# Schematics_2.net
KiCad netlist of a schematic drawn in EasyEDA
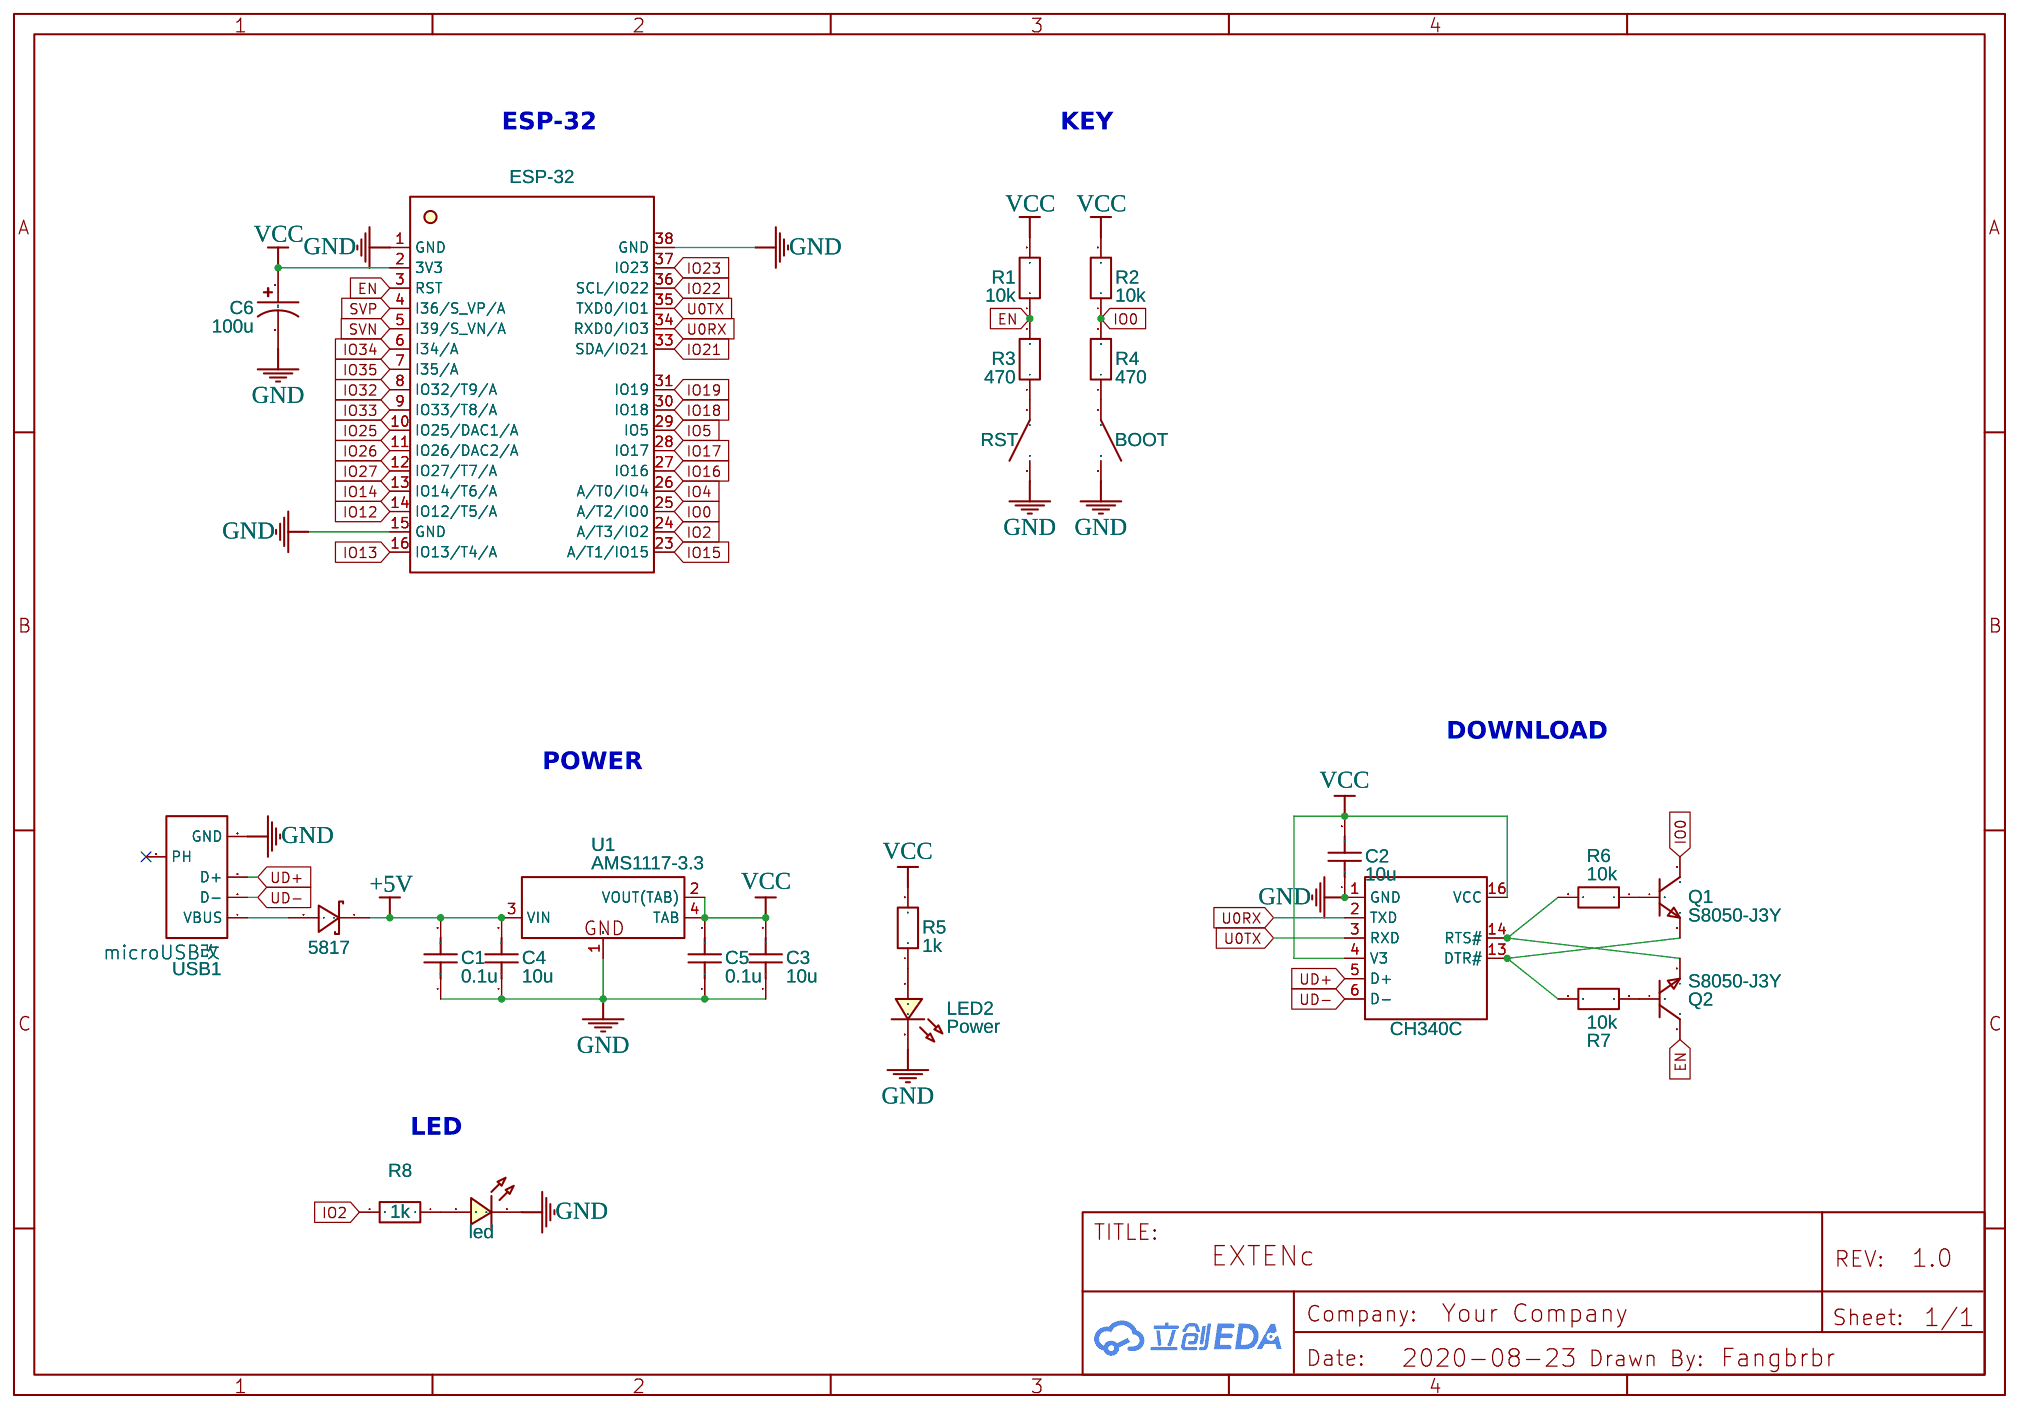
[diagram p0: Sheet_1]
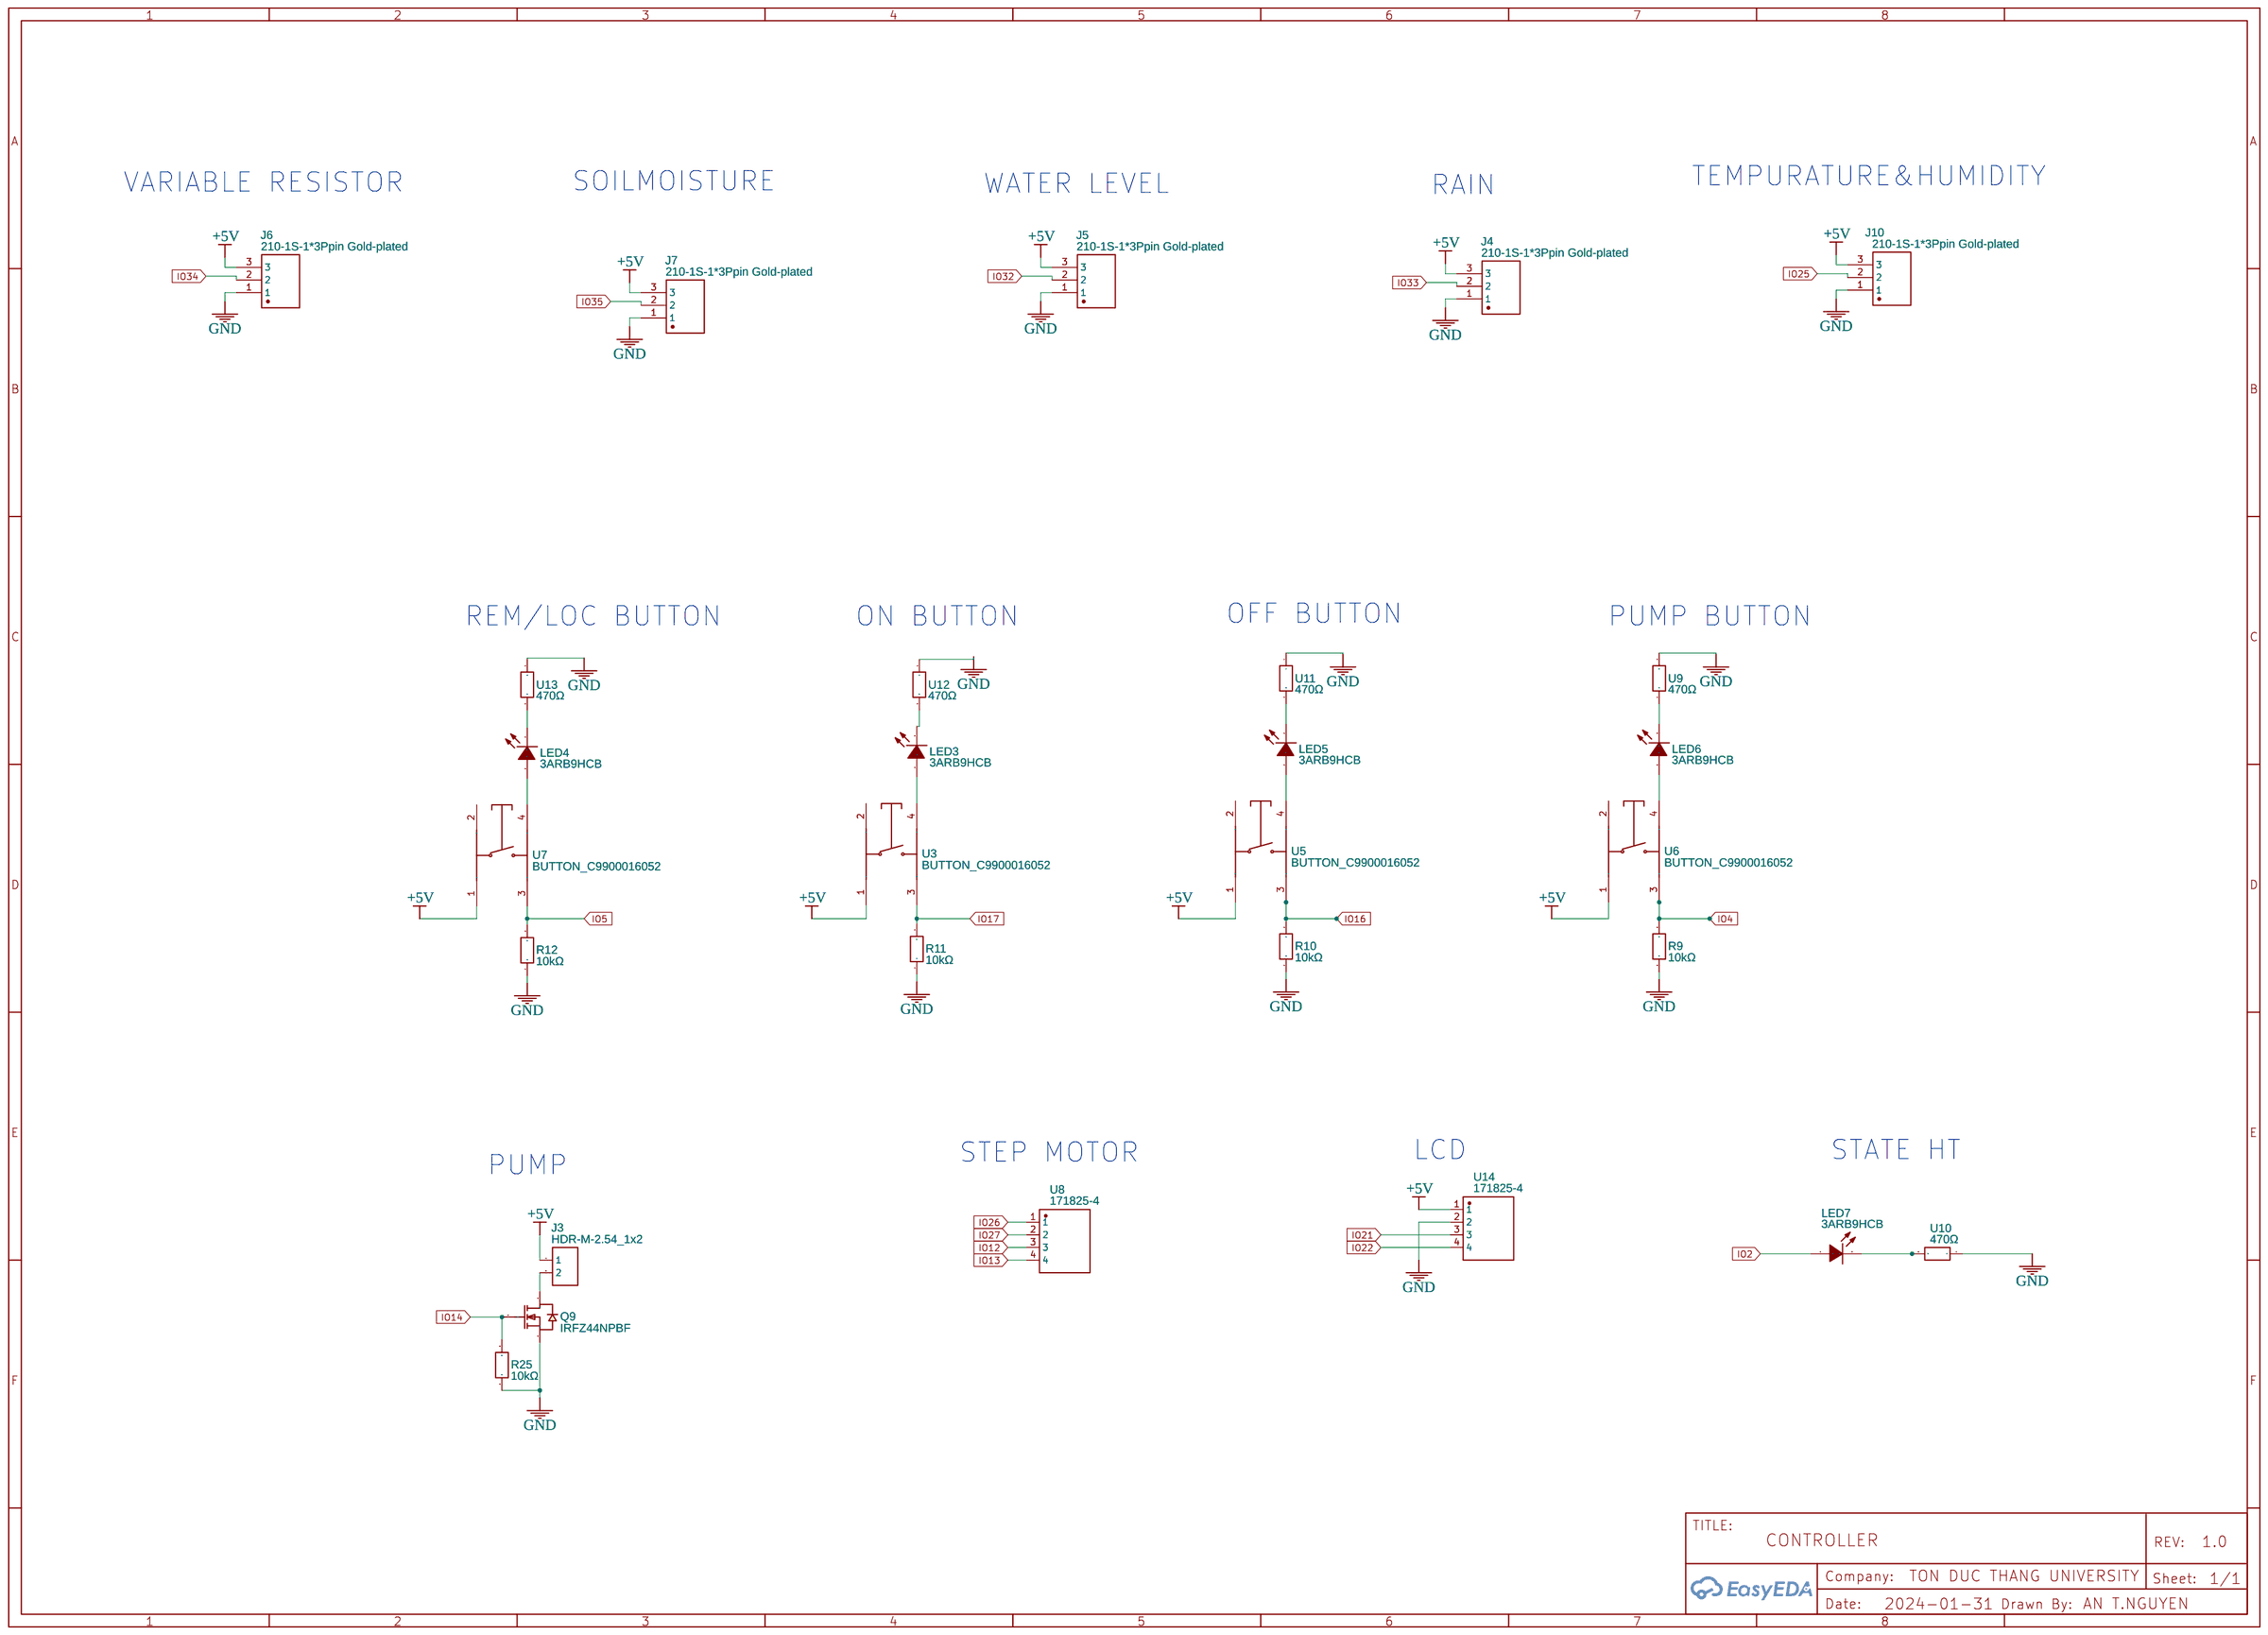
[diagram p1: Sheet_2]

(export (version "E")
  (design (tool "Eeschema 10.0.6"))
  (components
    (comp (ref "C1") (value "0.1u") (libsource (lib "") (part "C_0603_US")))
    (comp (ref "C2") (value "10u") (libsource (lib "") (part "C_0603_US")))
    (comp (ref "C3") (value "10u") (libsource (lib "") (part "C_0603_US")))
    (comp (ref "C4") (value "10u") (libsource (lib "") (part "C_0603_US")))
    (comp (ref "C5") (value "0.1u") (libsource (lib "") (part "C_0603_US")))
    (comp (ref "C6") (value "100u") (libsource (lib "") (part "C_Tan_SMD_B_US")))
    (comp (ref "D1")
      (value "5817")
      (fields
        (field (name "Manufacturer Part") "1N5819W")
        (field (name "Manufacturer") "Shandong Jingdao Microelectronics")
      )
      (libsource (lib "") (part "1N5819W"))
    )
    (comp (ref "LED1")
      (value "led")
      (fields
        (field (name "Manufacturer Part") "19-217/R6C-AL1M2VY/3T")
        (field (name "Manufacturer") "EVERLIGHT(台湾亿光)")
      )
      (libsource (lib "") (part "LED-0603_R"))
    )
    (comp (ref "LED2")
      (value "Power")
      (fields
        (field (name "Manufacturer Part") "19-217/R6C-AL1M2VY/3T")
        (field (name "Manufacturer") "EVERLIGHT(台湾亿光)")
      )
      (libsource (lib "") (part "LED-0603_R_1"))
    )
    (comp (ref "Q1")
      (value "S8050-J3Y")
      (fields (field (name "Manufacturer") "(MDD) Jiangsu Yutai Elec"))
      (libsource (lib "") (part "S8050-J3Y"))
    )
    (comp (ref "Q2")
      (value "S8050-J3Y")
      (fields (field (name "Manufacturer") "(MDD) Jiangsu Yutai Elec"))
      (libsource (lib "") (part "S8050-J3Y_1"))
    )
    (comp (ref "R1") (value "10k") (libsource (lib "") (part "R_0603_EU")))
    (comp (ref "R2") (value "10k") (libsource (lib "") (part "R_0603_EU")))
    (comp (ref "R3") (value "470") (libsource (lib "") (part "R_0603_EU")))
    (comp (ref "R4") (value "470") (libsource (lib "") (part "R_0603_EU")))
    (comp (ref "R5") (value "1k") (libsource (lib "") (part "R_0603_EU")))
    (comp (ref "R6") (value "10k") (libsource (lib "") (part "R_0603_EU_1")))
    (comp (ref "R7") (value "10k") (libsource (lib "") (part "R_0603_EU_1")))
    (comp (ref "R8") (value "1k") (libsource (lib "") (part "R_0603_EU_1")))
    (comp (ref "SW1")
      (value "RST")
      (fields (field (name "Manufacturer Part") "TSA343G00D-250J2") (field (name "Manufacturer") "BRIGHT"))
      (libsource (lib "") (part "龟仔按键-带柱"))
    )
    (comp (ref "SW2")
      (value "BOOT")
      (fields (field (name "Manufacturer Part") "TSA343G00D-250J2") (field (name "Manufacturer") "BRIGHT"))
      (libsource (lib "") (part "龟仔按键-带柱_1"))
    )
    (comp (ref "U1")
      (value "AMS1117-3.3")
      (fields (field (name "Manufacturer") "Youtai Semiconductor Co., Ltd."))
      (libsource (lib "") (part "AMS1117-3.3"))
    )
    (comp (ref "U2")
      (value "CH340C")
      (fields (field (name "Manufacturer") "WCH"))
      (libsource (lib "") (part "CH340C"))
    )
    (comp (ref "U4")
      (value "ESP-32")
      (fields (field (name "Manufacturer Part") "ESP-32S") (field (name "Manufacturer") "Ai-Thinker"))
      (libsource (lib "") (part "安信可ESP-32S"))
    )
    (comp (ref "USB1")
      (value "microUSB改")
      (fields (field (name "Manufacturer Part") "MICRO5.9mmusb") (field (name "Manufacturer") "SHOU HAN"))
      (libsource (lib "") (part "microUSB改"))
    )
    (comp (ref "J3") (value "HDR-M-2.54_1x2") (libsource (lib "") (part "HDR-M-2.54_1x2")))
    (comp (ref "J4")
      (value "210-1S-1*3Ppin Gold-plated")
      (fields (field (name "Manufacturer") "Ckmtw"))
      (libsource (lib "") (part "210-1S-1*3Ppin Gold-plated"))
    )
    (comp (ref "J5")
      (value "210-1S-1*3Ppin Gold-plated")
      (fields (field (name "Manufacturer") "Ckmtw"))
      (libsource (lib "") (part "210-1S-1*3Ppin Gold-plated"))
    )
    (comp (ref "J6")
      (value "210-1S-1*3Ppin Gold-plated")
      (fields (field (name "Manufacturer") "Ckmtw"))
      (libsource (lib "") (part "210-1S-1*3Ppin Gold-plated"))
    )
    (comp (ref "J7")
      (value "210-1S-1*3Ppin Gold-plated")
      (fields (field (name "Manufacturer") "Ckmtw"))
      (libsource (lib "") (part "210-1S-1*3Ppin Gold-plated"))
    )
    (comp (ref "J10")
      (value "210-1S-1*3Ppin Gold-plated")
      (fields (field (name "Manufacturer") "Ckmtw"))
      (libsource (lib "") (part "210-1S-1*3Ppin Gold-plated"))
    )
    (comp (ref "LED3")
      (value "3ARB9HCB")
      (fields (field (name "Manufacturer") "KENTO"))
      (libsource (lib "") (part "3ARB9HCB"))
    )
    (comp (ref "LED4")
      (value "3ARB9HCB")
      (fields (field (name "Manufacturer") "KENTO"))
      (libsource (lib "") (part "3ARB9HCB"))
    )
    (comp (ref "LED5")
      (value "3ARB9HCB")
      (fields (field (name "Manufacturer") "KENTO"))
      (libsource (lib "") (part "3ARB9HCB"))
    )
    (comp (ref "LED6")
      (value "3ARB9HCB")
      (fields (field (name "Manufacturer") "KENTO"))
      (libsource (lib "") (part "3ARB9HCB"))
    )
    (comp (ref "LED7")
      (value "3ARB9HCB")
      (fields (field (name "Manufacturer") "KENTO"))
      (libsource (lib "") (part "3ARB9HCB_1"))
    )
    (comp (ref "Q9")
      (value "IRFZ44NPBF")
      (fields (field (name "Manufacturer") "Infineon(英飞凌)"))
      (libsource (lib "") (part "IRFZ44NPBF"))
    )
    (comp (ref "R9")
      (value "10kΩ")
      (fields (field (name "Manufacturer Part") "CMF5010K000FHEB") (field (name "Manufacturer") "VISHAY(威世)"))
      (libsource (lib "") (part "CMF5010K000FHEB"))
    )
    (comp (ref "R10")
      (value "10kΩ")
      (fields (field (name "Manufacturer Part") "CMF5010K000FHEB") (field (name "Manufacturer") "VISHAY(威世)"))
      (libsource (lib "") (part "CMF5010K000FHEB"))
    )
    (comp (ref "R11")
      (value "10kΩ")
      (fields (field (name "Manufacturer Part") "CMF5010K000FHEB") (field (name "Manufacturer") "VISHAY(威世)"))
      (libsource (lib "") (part "CMF5010K000FHEB"))
    )
    (comp (ref "R12")
      (value "10kΩ")
      (fields (field (name "Manufacturer Part") "CMF5010K000FHEB") (field (name "Manufacturer") "VISHAY(威世)"))
      (libsource (lib "") (part "CMF5010K000FHEB"))
    )
    (comp (ref "R25")
      (value "10kΩ")
      (fields (field (name "Manufacturer Part") "CMF5010K000FHEB") (field (name "Manufacturer") "VISHAY(威世)"))
      (libsource (lib "") (part "CMF5010K000FHEB"))
    )
    (comp (ref "U3")
      (value "BUTTON_C9900016052")
      (fields (field (name "Manufacturer Part") "button"))
      (libsource (lib "") (part "BUTTON_C9900016052"))
    )
    (comp (ref "U5")
      (value "BUTTON_C9900016052")
      (fields (field (name "Manufacturer Part") "button"))
      (libsource (lib "") (part "BUTTON_C9900016052"))
    )
    (comp (ref "U6")
      (value "BUTTON_C9900016052")
      (fields (field (name "Manufacturer Part") "button"))
      (libsource (lib "") (part "BUTTON_C9900016052"))
    )
    (comp (ref "U7")
      (value "BUTTON_C9900016052")
      (fields (field (name "Manufacturer Part") "button"))
      (libsource (lib "") (part "BUTTON_C9900016052"))
    )
    (comp (ref "U8")
      (value "171825-4")
      (fields (field (name "Manufacturer") "TE Connectivity(泰科电子)"))
      (libsource (lib "") (part "171825-4"))
    )
    (comp (ref "U9")
      (value "470Ω")
      (fields (field (name "Manufacturer Part") "CF1/4W-470Ω±5%T52") (field (name "Manufacturer") "华星机电"))
      (libsource (lib "") (part "CF1/4W-470Ω±5%T52_2"))
    )
    (comp (ref "U10")
      (value "470Ω")
      (fields (field (name "Manufacturer Part") "CF1/4W-470Ω±5%T52") (field (name "Manufacturer") "华星机电"))
      (libsource (lib "") (part "CF1/4W-470Ω±5%T52_1"))
    )
    (comp (ref "U11")
      (value "470Ω")
      (fields (field (name "Manufacturer Part") "CF1/4W-470Ω±5%T52") (field (name "Manufacturer") "华星机电"))
      (libsource (lib "") (part "CF1/4W-470Ω±5%T52"))
    )
    (comp (ref "U12")
      (value "470Ω")
      (fields (field (name "Manufacturer Part") "CF1/4W-470Ω±5%T52") (field (name "Manufacturer") "华星机电"))
      (libsource (lib "") (part "CF1/4W-470Ω±5%T52"))
    )
    (comp (ref "U13")
      (value "470Ω")
      (fields (field (name "Manufacturer Part") "CF1/4W-470Ω±5%T52") (field (name "Manufacturer") "华星机电"))
      (libsource (lib "") (part "CF1/4W-470Ω±5%T52"))
    )
    (comp (ref "U14")
      (value "171825-4")
      (fields (field (name "Manufacturer") "TE Connectivity(泰科电子)"))
      (libsource (lib "") (part "171825-4"))
    )
  )
  (nets
    (net (code "1") (name "+5V") (class "Default")
      (node (ref "C1") (pin "2") (pinfunction "2_2") (pintype "unspecified"))
      (node (ref "C4") (pin "2") (pinfunction "2_2") (pintype "unspecified"))
      (node (ref "D1") (pin "1") (pinfunction "1_1") (pintype "unspecified"))
      (node (ref "J10") (pin "3") (pinfunction "3_3") (pintype "unspecified"))
      (node (ref "J3") (pin "1") (pinfunction "1_1") (pintype "unspecified"))
      (node (ref "J4") (pin "3") (pinfunction "3_3") (pintype "unspecified"))
      (node (ref "J5") (pin "3") (pinfunction "3_3") (pintype "unspecified"))
      (node (ref "J6") (pin "3") (pinfunction "3_3") (pintype "unspecified"))
      (node (ref "J7") (pin "3") (pinfunction "3_3") (pintype "unspecified"))
      (node (ref "U1") (pin "3") (pinfunction "VIN_3") (pintype "unspecified"))
      (node (ref "U14") (pin "1") (pinfunction "1_1") (pintype "unspecified"))
      (node (ref "U3") (pin "1") (pinfunction "1_1") (pintype "unspecified"))
      (node (ref "U5") (pin "1") (pinfunction "1_1") (pintype "unspecified"))
      (node (ref "U6") (pin "1") (pinfunction "1_1") (pintype "unspecified"))
      (node (ref "U7") (pin "1") (pinfunction "1_1") (pintype "unspecified"))
    )
    (net (code "2") (name "EN") (class "Default")
      (node (ref "Q2") (pin "3") (pinfunction "C_3") (pintype "unspecified"))
      (node (ref "R1") (pin "1") (pinfunction "1_1") (pintype "unspecified"))
      (node (ref "R3") (pin "2") (pinfunction "2_2") (pintype "unspecified"))
      (node (ref "U4") (pin "3") (pinfunction "RST_3") (pintype "unspecified"))
    )
    (net (code "3") (name "GND") (class "Default")
      (node (ref "C1") (pin "1") (pinfunction "1_1") (pintype "unspecified"))
      (node (ref "C2") (pin "1") (pinfunction "1_1") (pintype "unspecified"))
      (node (ref "C3") (pin "1") (pinfunction "1_1") (pintype "unspecified"))
      (node (ref "C4") (pin "1") (pinfunction "1_1") (pintype "unspecified"))
      (node (ref "C5") (pin "1") (pinfunction "1_1") (pintype "unspecified"))
      (node (ref "C6") (pin "2") (pinfunction "2_2") (pintype "unspecified"))
      (node (ref "J10") (pin "1") (pinfunction "1_1") (pintype "unspecified"))
      (node (ref "J4") (pin "1") (pinfunction "1_1") (pintype "unspecified"))
      (node (ref "J5") (pin "1") (pinfunction "1_1") (pintype "unspecified"))
      (node (ref "J6") (pin "1") (pinfunction "1_1") (pintype "unspecified"))
      (node (ref "J7") (pin "1") (pinfunction "1_1") (pintype "unspecified"))
      (node (ref "LED1") (pin "2") (pinfunction "2_2") (pintype "unspecified"))
      (node (ref "LED2") (pin "2") (pinfunction "2_2") (pintype "unspecified"))
      (node (ref "Q9") (pin "3") (pinfunction "S_3") (pintype "unspecified"))
      (node (ref "R10") (pin "1") (pinfunction "1_1") (pintype "unspecified"))
      (node (ref "R11") (pin "1") (pinfunction "1_1") (pintype "unspecified"))
      (node (ref "R12") (pin "1") (pinfunction "1_1") (pintype "unspecified"))
      (node (ref "R25") (pin "1") (pinfunction "1_1") (pintype "unspecified"))
      (node (ref "R9") (pin "1") (pinfunction "1_1") (pintype "unspecified"))
      (node (ref "SW1") (pin "2") (pinfunction "2_2") (pintype "input"))
      (node (ref "SW2") (pin "2") (pinfunction "2_2") (pintype "input"))
      (node (ref "U1") (pin "1") (pinfunction "ADJ(GND)_1") (pintype "unspecified"))
      (node (ref "U10") (pin "1") (pinfunction "1_1") (pintype "unspecified"))
      (node (ref "U11") (pin "1") (pinfunction "1_1") (pintype "unspecified"))
      (node (ref "U12") (pin "1") (pinfunction "1_1") (pintype "unspecified"))
      (node (ref "U13") (pin "1") (pinfunction "1_1") (pintype "unspecified"))
      (node (ref "U14") (pin "2") (pinfunction "2_2") (pintype "unspecified"))
      (node (ref "U2") (pin "1") (pinfunction "GND_1") (pintype "unspecified"))
      (node (ref "U4") (pin "1") (pinfunction "GND_1") (pintype "unspecified"))
      (node (ref "U4") (pin "15") (pinfunction "GND_15") (pintype "unspecified"))
      (node (ref "U4") (pin "38") (pinfunction "GND_38") (pintype "unspecified"))
      (node (ref "U9") (pin "2") (pinfunction "2_2") (pintype "unspecified"))
      (node (ref "USB1") (pin "5") (pinfunction "GND_5") (pintype "unspecified"))
    )
    (net (code "4") (name "IO0") (class "Default")
      (node (ref "Q1") (pin "3") (pinfunction "C_3") (pintype "unspecified"))
      (node (ref "R2") (pin "1") (pinfunction "1_1") (pintype "unspecified"))
      (node (ref "R4") (pin "2") (pinfunction "2_2") (pintype "unspecified"))
      (node (ref "U4") (pin "25") (pinfunction "A/T2/IO0_25") (pintype "unspecified"))
    )
    (net (code "5") (name "IO2") (class "Default")
      (node (ref "LED7") (pin "1") (pinfunction "A_1") (pintype "unspecified"))
      (node (ref "R8") (pin "2") (pinfunction "2_2") (pintype "unspecified"))
      (node (ref "U4") (pin "24") (pinfunction "A/T3/IO2_24") (pintype "unspecified"))
    )
    (net (code "6") (name "IO4") (class "Default")
      (node (ref "R9") (pin "2") (pinfunction "2_2") (pintype "unspecified"))
      (node (ref "U4") (pin "26") (pinfunction "A/T0/IO4_26") (pintype "unspecified"))
      (node (ref "U6") (pin "3") (pinfunction "3_3") (pintype "unspecified"))
    )
    (net (code "7") (name "IO5") (class "Default")
      (node (ref "R12") (pin "2") (pinfunction "2_2") (pintype "unspecified"))
      (node (ref "U4") (pin "29") (pinfunction "IO5_29") (pintype "unspecified"))
      (node (ref "U7") (pin "3") (pinfunction "3_3") (pintype "unspecified"))
    )
    (net (code "8") (name "IO12") (class "Default")
      (node (ref "U4") (pin "14") (pinfunction "IO12/T5/A_14") (pintype "unspecified"))
      (node (ref "U8") (pin "3") (pinfunction "3_3") (pintype "unspecified"))
    )
    (net (code "9") (name "IO13") (class "Default")
      (node (ref "U4") (pin "16") (pinfunction "IO13/T4/A_16") (pintype "unspecified"))
      (node (ref "U8") (pin "4") (pinfunction "4_4") (pintype "unspecified"))
    )
    (net (code "10") (name "IO14") (class "Default")
      (node (ref "Q9") (pin "1") (pinfunction "G_1") (pintype "unspecified"))
      (node (ref "R25") (pin "2") (pinfunction "2_2") (pintype "unspecified"))
      (node (ref "U4") (pin "13") (pinfunction "IO14/T6/A_13") (pintype "unspecified"))
    )
    (net (code "11") (name "IO15") (class "Default")
      (node (ref "U4") (pin "23") (pinfunction "A/T1/IO15_23") (pintype "unspecified"))
    )
    (net (code "12") (name "IO16") (class "Default")
      (node (ref "R10") (pin "2") (pinfunction "2_2") (pintype "unspecified"))
      (node (ref "U4") (pin "27") (pinfunction "IO16_27") (pintype "unspecified"))
      (node (ref "U5") (pin "3") (pinfunction "3_3") (pintype "unspecified"))
    )
    (net (code "13") (name "IO17") (class "Default")
      (node (ref "R11") (pin "2") (pinfunction "2_2") (pintype "unspecified"))
      (node (ref "U3") (pin "3") (pinfunction "3_3") (pintype "unspecified"))
      (node (ref "U4") (pin "28") (pinfunction "IO17_28") (pintype "unspecified"))
    )
    (net (code "14") (name "IO18") (class "Default")
      (node (ref "U4") (pin "30") (pinfunction "IO18_30") (pintype "unspecified"))
    )
    (net (code "15") (name "IO19") (class "Default")
      (node (ref "U4") (pin "31") (pinfunction "IO19_31") (pintype "unspecified"))
    )
    (net (code "16") (name "IO21") (class "Default")
      (node (ref "U14") (pin "3") (pinfunction "3_3") (pintype "unspecified"))
      (node (ref "U4") (pin "33") (pinfunction "SDA/IO21_33") (pintype "unspecified"))
    )
    (net (code "17") (name "IO22") (class "Default")
      (node (ref "U14") (pin "4") (pinfunction "4_4") (pintype "unspecified"))
      (node (ref "U4") (pin "36") (pinfunction "SCL/IO22_36") (pintype "unspecified"))
    )
    (net (code "18") (name "IO23") (class "Default")
      (node (ref "U4") (pin "37") (pinfunction "IO23_37") (pintype "unspecified"))
    )
    (net (code "19") (name "IO25") (class "Default")
      (node (ref "J10") (pin "2") (pinfunction "2_2") (pintype "unspecified"))
      (node (ref "U4") (pin "10") (pinfunction "IO25/DAC1/A_10") (pintype "unspecified"))
    )
    (net (code "20") (name "IO26") (class "Default")
      (node (ref "U4") (pin "11") (pinfunction "IO26/DAC2/A_11") (pintype "unspecified"))
      (node (ref "U8") (pin "1") (pinfunction "1_1") (pintype "unspecified"))
    )
    (net (code "21") (name "IO27") (class "Default")
      (node (ref "U4") (pin "12") (pinfunction "IO27/T7/A_12") (pintype "unspecified"))
      (node (ref "U8") (pin "2") (pinfunction "2_2") (pintype "unspecified"))
    )
    (net (code "22") (name "IO32") (class "Default")
      (node (ref "J5") (pin "2") (pinfunction "2_2") (pintype "unspecified"))
      (node (ref "U4") (pin "8") (pinfunction "IO32/T9/A_8") (pintype "unspecified"))
    )
    (net (code "23") (name "IO33") (class "Default")
      (node (ref "J4") (pin "2") (pinfunction "2_2") (pintype "unspecified"))
      (node (ref "U4") (pin "9") (pinfunction "IO33/T8/A_9") (pintype "unspecified"))
    )
    (net (code "24") (name "IO34") (class "Default")
      (node (ref "J6") (pin "2") (pinfunction "2_2") (pintype "unspecified"))
      (node (ref "U4") (pin "6") (pinfunction "I34/A_6") (pintype "unspecified"))
    )
    (net (code "25") (name "IO35") (class "Default")
      (node (ref "J7") (pin "2") (pinfunction "2_2") (pintype "unspecified"))
      (node (ref "U4") (pin "7") (pinfunction "I35/A_7") (pintype "unspecified"))
    )
    (net (code "26") (name "Net-(LED1-Pad1)") (class "Default")
      (node (ref "LED1") (pin "1") (pinfunction "1_1") (pintype "unspecified"))
      (node (ref "R8") (pin "1") (pinfunction "1_1") (pintype "unspecified"))
    )
    (net (code "27") (name "Net-(LED2-Pad1)") (class "Default")
      (node (ref "LED2") (pin "1") (pinfunction "1_1") (pintype "unspecified"))
      (node (ref "R5") (pin "1") (pinfunction "1_1") (pintype "unspecified"))
    )
    (net (code "28") (name "Net-(LED3-A)") (class "Default")
      (node (ref "LED3") (pin "1") (pinfunction "A_1") (pintype "unspecified"))
      (node (ref "U3") (pin "4") (pinfunction "4_4") (pintype "unspecified"))
    )
    (net (code "29") (name "Net-(LED3-K)") (class "Default")
      (node (ref "LED3") (pin "2") (pinfunction "K_2") (pintype "unspecified"))
      (node (ref "U12") (pin "2") (pinfunction "2_2") (pintype "unspecified"))
    )
    (net (code "30") (name "Net-(LED4-A)") (class "Default")
      (node (ref "LED4") (pin "1") (pinfunction "A_1") (pintype "unspecified"))
      (node (ref "U7") (pin "4") (pinfunction "4_4") (pintype "unspecified"))
    )
    (net (code "31") (name "Net-(LED4-K)") (class "Default")
      (node (ref "LED4") (pin "2") (pinfunction "K_2") (pintype "unspecified"))
      (node (ref "U13") (pin "2") (pinfunction "2_2") (pintype "unspecified"))
    )
    (net (code "32") (name "Net-(LED5-A)") (class "Default")
      (node (ref "LED5") (pin "1") (pinfunction "A_1") (pintype "unspecified"))
      (node (ref "U5") (pin "4") (pinfunction "4_4") (pintype "unspecified"))
    )
    (net (code "33") (name "Net-(LED5-K)") (class "Default")
      (node (ref "LED5") (pin "2") (pinfunction "K_2") (pintype "unspecified"))
      (node (ref "U11") (pin "2") (pinfunction "2_2") (pintype "unspecified"))
    )
    (net (code "34") (name "Net-(LED6-A)") (class "Default")
      (node (ref "LED6") (pin "1") (pinfunction "A_1") (pintype "unspecified"))
      (node (ref "U6") (pin "4") (pinfunction "4_4") (pintype "unspecified"))
    )
    (net (code "35") (name "Net-(LED6-K)") (class "Default")
      (node (ref "LED6") (pin "2") (pinfunction "K_2") (pintype "unspecified"))
      (node (ref "U9") (pin "1") (pinfunction "1_1") (pintype "unspecified"))
    )
    (net (code "36") (name "Net-(LED7-K)") (class "Default")
      (node (ref "LED7") (pin "2") (pinfunction "K_2") (pintype "unspecified"))
      (node (ref "U10") (pin "2") (pinfunction "2_2") (pintype "unspecified"))
    )
    (net (code "37") (name "Net-(Q1-B)") (class "Default")
      (node (ref "Q1") (pin "1") (pinfunction "B_1") (pintype "unspecified"))
      (node (ref "R6") (pin "1") (pinfunction "1_1") (pintype "unspecified"))
    )
    (net (code "38") (name "Net-(Q1-E)") (class "Default")
      (node (ref "Q1") (pin "2") (pinfunction "E_2") (pintype "unspecified"))
      (node (ref "R7") (pin "2") (pinfunction "2_2") (pintype "unspecified"))
      (node (ref "U2") (pin "13") (pinfunction "DTR#_13") (pintype "unspecified"))
    )
    (net (code "39") (name "Net-(Q2-B)") (class "Default")
      (node (ref "Q2") (pin "1") (pinfunction "B_1") (pintype "unspecified"))
      (node (ref "R7") (pin "1") (pinfunction "1_1") (pintype "unspecified"))
    )
    (net (code "40") (name "Net-(Q2-E)") (class "Default")
      (node (ref "Q2") (pin "2") (pinfunction "E_2") (pintype "unspecified"))
      (node (ref "R6") (pin "2") (pinfunction "2_2") (pintype "unspecified"))
      (node (ref "U2") (pin "14") (pinfunction "RTS#_14") (pintype "unspecified"))
    )
    (net (code "41") (name "Net-(Q9-D)") (class "Default")
      (node (ref "J3") (pin "2") (pinfunction "2_2") (pintype "unspecified"))
      (node (ref "Q9") (pin "2") (pinfunction "D_2") (pintype "unspecified"))
    )
    (net (code "42") (name "Net-(R3-Pad1)") (class "Default")
      (node (ref "R3") (pin "1") (pinfunction "1_1") (pintype "unspecified"))
      (node (ref "SW1") (pin "1") (pinfunction "1_1") (pintype "input"))
    )
    (net (code "43") (name "Net-(R4-Pad1)") (class "Default")
      (node (ref "R4") (pin "1") (pinfunction "1_1") (pintype "unspecified"))
      (node (ref "SW2") (pin "1") (pinfunction "1_1") (pintype "input"))
    )
    (net (code "44") (name "Net-(USB1-VBUS)") (class "Default")
      (node (ref "D1") (pin "2") (pinfunction "2_2") (pintype "unspecified"))
      (node (ref "USB1") (pin "1") (pinfunction "VBUS_1") (pintype "unspecified"))
    )
    (net (code "45") (name "SVN") (class "Default")
      (node (ref "U4") (pin "5") (pinfunction "I39/S_VN/A_5") (pintype "unspecified"))
    )
    (net (code "46") (name "SVP") (class "Default")
      (node (ref "U4") (pin "4") (pinfunction "I36/S_VP/A_4") (pintype "unspecified"))
    )
    (net (code "47") (name "U0RX") (class "Default")
      (node (ref "U2") (pin "2") (pinfunction "TXD_2") (pintype "unspecified"))
      (node (ref "U4") (pin "34") (pinfunction "RXD0/IO3_34") (pintype "unspecified"))
    )
    (net (code "48") (name "U0TX") (class "Default")
      (node (ref "U2") (pin "3") (pinfunction "RXD_3") (pintype "unspecified"))
      (node (ref "U4") (pin "35") (pinfunction "TXD0/IO1_35") (pintype "unspecified"))
    )
    (net (code "49") (name "UD+") (class "Default")
      (node (ref "U2") (pin "5") (pinfunction "D+_5") (pintype "unspecified"))
      (node (ref "USB1") (pin "3") (pinfunction "D+_3") (pintype "unspecified"))
    )
    (net (code "50") (name "UD-") (class "Default")
      (node (ref "U2") (pin "6") (pinfunction "D-_6") (pintype "unspecified"))
      (node (ref "USB1") (pin "2") (pinfunction "D-_2") (pintype "unspecified"))
    )
    (net (code "51") (name "VCC") (class "Default")
      (node (ref "C2") (pin "2") (pinfunction "2_2") (pintype "unspecified"))
      (node (ref "C3") (pin "2") (pinfunction "2_2") (pintype "unspecified"))
      (node (ref "C5") (pin "2") (pinfunction "2_2") (pintype "unspecified"))
      (node (ref "C6") (pin "1") (pinfunction "1_1") (pintype "unspecified"))
      (node (ref "R1") (pin "2") (pinfunction "2_2") (pintype "unspecified"))
      (node (ref "R2") (pin "2") (pinfunction "2_2") (pintype "unspecified"))
      (node (ref "R5") (pin "2") (pinfunction "2_2") (pintype "unspecified"))
      (node (ref "U1") (pin "2") (pinfunction "VOUT(TAB)_2") (pintype "unspecified"))
      (node (ref "U1") (pin "4") (pinfunction "TAB_4") (pintype "unspecified"))
      (node (ref "U2") (pin "16") (pinfunction "VCC_16") (pintype "unspecified"))
      (node (ref "U2") (pin "4") (pinfunction "V3_4") (pintype "unspecified"))
      (node (ref "U4") (pin "2") (pinfunction "3V3_2") (pintype "unspecified"))
    )
    (net (code "52") (name "unconnected-(U3-Pad2)") (class "Default")
      (node (ref "U3") (pin "2") (pinfunction "2_2") (pintype "unspecified"))
    )
    (net (code "53") (name "unconnected-(U5-Pad2)") (class "Default")
      (node (ref "U5") (pin "2") (pinfunction "2_2") (pintype "unspecified"))
    )
    (net (code "54") (name "unconnected-(U6-Pad2)") (class "Default")
      (node (ref "U6") (pin "2") (pinfunction "2_2") (pintype "unspecified"))
    )
    (net (code "55") (name "unconnected-(U7-Pad2)") (class "Default")
      (node (ref "U7") (pin "2") (pinfunction "2_2") (pintype "unspecified"))
    )
    (net (code "56") (name "unconnected-(USB1-PH-Pad0)") (class "Default")
      (node (ref "USB1") (pin "0") (pinfunction "PH_0") (pintype "unspecified+no_connect"))
    )
  )
)
